# Amplifier.net
KiCad netlist of a schematic drawn in Altium Designer
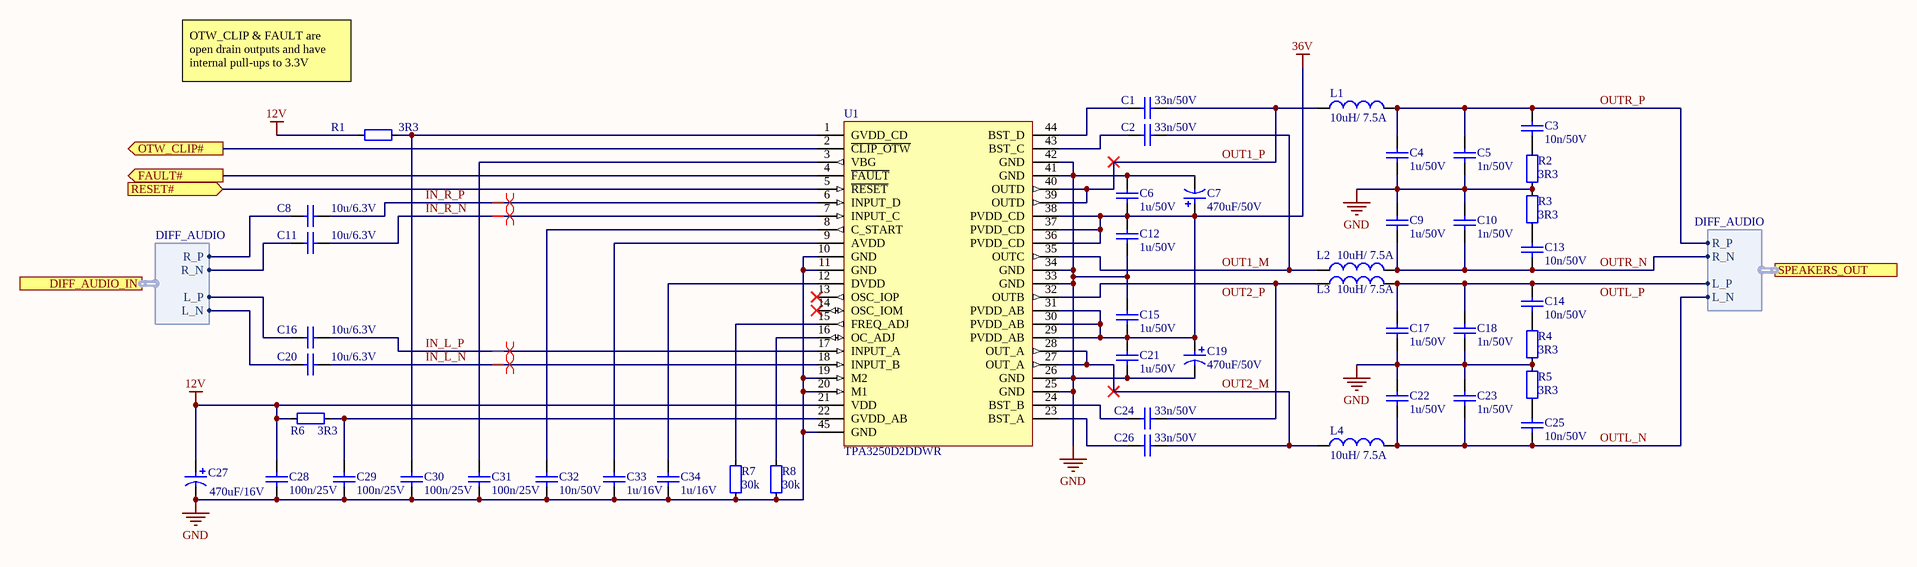
[diagram p0: Amplifier.SchDoc]

(export (version "E")
  (design (tool "Eeschema 10.0.6"))
  (components
    (comp (ref "C1")
      (value "33n/50V")
      (footprint "C0603")
      (fields (field (name "VOLTAGE") "50V") (field (name "TOLERANCE") "10%"))
      (libsource (lib "dk_capacitors") (part "33n 50V X7R 0603"))
    )
    (comp (ref "C2")
      (value "33n/50V")
      (footprint "C0603")
      (fields (field (name "VOLTAGE") "50V") (field (name "TOLERANCE") "10%"))
      (libsource (lib "dk_capacitors") (part "33n 50V X7R 0603"))
    )
    (comp (ref "C3")
      (value "10n/50V")
      (footprint "C0402")
      (fields (field (name "VOLTAGE") "50V") (field (name "TOLERANCE") "10%"))
      (libsource (lib "dk_capacitors") (part "10n 50V X7R 0402"))
    )
    (comp (ref "C4")
      (value "1u/50V")
      (footprint "C2824")
      (fields (field (name "VOLTAGE") "50V") (field (name "TOLERANCE") "5%"))
      (libsource (lib "dk_capacitors") (part "1u 50V PET 2824"))
    )
    (comp (ref "C5")
      (value "1n/50V")
      (footprint "C0402")
      (fields (field (name "VOLTAGE") "50V") (field (name "TOLERANCE") "10%"))
      (libsource (lib "dk_capacitors") (part "1n 50V X7R 0402"))
    )
    (comp (ref "C6")
      (value "1u/50V")
      (footprint "C0805")
      (fields (field (name "VOLTAGE") "50V") (field (name "TOLERANCE") "10%"))
      (libsource (lib "dk_capacitors") (part "1u 50V X7R 0805"))
    )
    (comp (ref "C7")
      (value "470uF/50V")
      (footprint "Wurth-L17-D16")
      (description "Aluminium Electrolytic Capacitors - SMD WCAP-ASLL 50V 470uF 20% ESR=73mOhms")
      (fields (field (name "VOLTAGE") "50V") (field (name "TOLERANCE") "20%"))
      (libsource (lib "dk_electrolytic_caps") (part "Wurth-470uF-50V-L17-D16"))
    )
    (comp (ref "C8")
      (value "10u/6.3V")
      (footprint "C0805")
      (fields (field (name "VOLTAGE") "6.3V") (field (name "TOLERANCE") "10%"))
      (libsource (lib "dk_capacitors") (part "10u 6V3 X7R 0805"))
    )
    (comp (ref "C9")
      (value "1u/50V")
      (footprint "C2824")
      (fields (field (name "VOLTAGE") "50V") (field (name "TOLERANCE") "5%"))
      (libsource (lib "dk_capacitors") (part "1u 50V PET 2824"))
    )
    (comp (ref "C10")
      (value "1n/50V")
      (footprint "C0402")
      (fields (field (name "VOLTAGE") "50V") (field (name "TOLERANCE") "10%"))
      (libsource (lib "dk_capacitors") (part "1n 50V X7R 0402"))
    )
    (comp (ref "C11")
      (value "10u/6.3V")
      (footprint "C0805")
      (fields (field (name "VOLTAGE") "6.3V") (field (name "TOLERANCE") "10%"))
      (libsource (lib "dk_capacitors") (part "10u 6V3 X7R 0805"))
    )
    (comp (ref "C12")
      (value "1u/50V")
      (footprint "C0805")
      (fields (field (name "VOLTAGE") "50V") (field (name "TOLERANCE") "10%"))
      (libsource (lib "dk_capacitors") (part "1u 50V X7R 0805"))
    )
    (comp (ref "C13")
      (value "10n/50V")
      (footprint "C0402")
      (fields (field (name "VOLTAGE") "50V") (field (name "TOLERANCE") "10%"))
      (libsource (lib "dk_capacitors") (part "10n 50V X7R 0402"))
    )
    (comp (ref "C14")
      (value "10n/50V")
      (footprint "C0402")
      (fields (field (name "VOLTAGE") "50V") (field (name "TOLERANCE") "10%"))
      (libsource (lib "dk_capacitors") (part "10n 50V X7R 0402"))
    )
    (comp (ref "C15")
      (value "1u/50V")
      (footprint "C0805")
      (fields (field (name "VOLTAGE") "50V") (field (name "TOLERANCE") "10%"))
      (libsource (lib "dk_capacitors") (part "1u 50V X7R 0805"))
    )
    (comp (ref "C16")
      (value "10u/6.3V")
      (footprint "C0805")
      (fields (field (name "VOLTAGE") "6.3V") (field (name "TOLERANCE") "10%"))
      (libsource (lib "dk_capacitors") (part "10u 6V3 X7R 0805"))
    )
    (comp (ref "C17")
      (value "1u/50V")
      (footprint "C2824")
      (fields (field (name "VOLTAGE") "50V") (field (name "TOLERANCE") "5%"))
      (libsource (lib "dk_capacitors") (part "1u 50V PET 2824"))
    )
    (comp (ref "C18")
      (value "1n/50V")
      (footprint "C0402")
      (fields (field (name "VOLTAGE") "50V") (field (name "TOLERANCE") "10%"))
      (libsource (lib "dk_capacitors") (part "1n 50V X7R 0402"))
    )
    (comp (ref "C19")
      (value "470uF/50V")
      (footprint "Wurth-L17-D16")
      (description "Aluminium Electrolytic Capacitors - SMD WCAP-ASLL 50V 470uF 20% ESR=73mOhms")
      (fields (field (name "VOLTAGE") "50V") (field (name "TOLERANCE") "20%"))
      (libsource (lib "dk_electrolytic_caps") (part "Wurth-470uF-50V-L17-D16"))
    )
    (comp (ref "C20")
      (value "10u/6.3V")
      (footprint "C0805")
      (fields (field (name "VOLTAGE") "6.3V") (field (name "TOLERANCE") "10%"))
      (libsource (lib "dk_capacitors") (part "10u 6V3 X7R 0805"))
    )
    (comp (ref "C21")
      (value "1u/50V")
      (footprint "C0805")
      (fields (field (name "VOLTAGE") "50V") (field (name "TOLERANCE") "10%"))
      (libsource (lib "dk_capacitors") (part "1u 50V X7R 0805"))
    )
    (comp (ref "C22")
      (value "1u/50V")
      (footprint "C2824")
      (fields (field (name "VOLTAGE") "50V") (field (name "TOLERANCE") "5%"))
      (libsource (lib "dk_capacitors") (part "1u 50V PET 2824"))
    )
    (comp (ref "C23")
      (value "1n/50V")
      (footprint "C0402")
      (fields (field (name "VOLTAGE") "50V") (field (name "TOLERANCE") "10%"))
      (libsource (lib "dk_capacitors") (part "1n 50V X7R 0402"))
    )
    (comp (ref "C24")
      (value "33n/50V")
      (footprint "C0603")
      (fields (field (name "VOLTAGE") "50V") (field (name "TOLERANCE") "10%"))
      (libsource (lib "dk_capacitors") (part "33n 50V X7R 0603"))
    )
    (comp (ref "C25")
      (value "10n/50V")
      (footprint "C0402")
      (fields (field (name "VOLTAGE") "50V") (field (name "TOLERANCE") "10%"))
      (libsource (lib "dk_capacitors") (part "10n 50V X7R 0402"))
    )
    (comp (ref "C26")
      (value "33n/50V")
      (footprint "C0603")
      (fields (field (name "VOLTAGE") "50V") (field (name "TOLERANCE") "10%"))
      (libsource (lib "dk_capacitors") (part "33n 50V X7R 0603"))
    )
    (comp (ref "C27")
      (value "470uF/16V")
      (footprint "Wurth-L10.5-D8")
      (description "Aluminium Electrolytic Capacitors - SMD WCAP-ASLI 470uF 16V 20% SMD/SMT")
      (fields (field (name "VOLTAGE") "16V") (field (name "TOLERANCE") "20%"))
      (libsource (lib "dk_electrolytic_caps") (part "Wurth-470uF-16V-L10.5-D8"))
    )
    (comp (ref "C28")
      (value "100n/25V")
      (footprint "C0402")
      (fields (field (name "VOLTAGE") "25V") (field (name "TOLERANCE") "10%"))
      (libsource (lib "dk_capacitors") (part "100n 25V X7R 0402"))
    )
    (comp (ref "C29")
      (value "100n/25V")
      (footprint "C0402")
      (fields (field (name "VOLTAGE") "25V") (field (name "TOLERANCE") "10%"))
      (libsource (lib "dk_capacitors") (part "100n 25V X7R 0402"))
    )
    (comp (ref "C30")
      (value "100n/25V")
      (footprint "C0402")
      (fields (field (name "VOLTAGE") "25V") (field (name "TOLERANCE") "10%"))
      (libsource (lib "dk_capacitors") (part "100n 25V X7R 0402"))
    )
    (comp (ref "C31")
      (value "100n/25V")
      (footprint "C0402")
      (fields (field (name "VOLTAGE") "25V") (field (name "TOLERANCE") "10%"))
      (libsource (lib "dk_capacitors") (part "100n 25V X7R 0402"))
    )
    (comp (ref "C32")
      (value "10n/50V")
      (footprint "C0402")
      (fields (field (name "VOLTAGE") "50V") (field (name "TOLERANCE") "10%"))
      (libsource (lib "dk_capacitors") (part "10n 50V X7R 0402"))
    )
    (comp (ref "C33")
      (value "1u/16V")
      (footprint "C0603")
      (fields (field (name "VOLTAGE") "16V") (field (name "TOLERANCE") "10%"))
      (libsource (lib "dk_capacitors") (part "1u 16V X7R 0603"))
    )
    (comp (ref "C34")
      (value "1u/16V")
      (footprint "C0603")
      (fields (field (name "VOLTAGE") "16V") (field (name "TOLERANCE") "10%"))
      (libsource (lib "dk_capacitors") (part "1u 16V X7R 0603"))
    )
    (comp (ref "L1")
      (value "10uH/ 7.5A")
      (footprint "PA4342.103NLT")
      (description "Fixed Inductors 10uH 7.5A 4mm 20% Low Prof")
      (fields (field (name "TOLERANCE") "20%") (field (name "MANUFACTURER PART NUMBER") "PA4342.103NLT"))
      (libsource (lib "dk_inductors") (part "PA4342.103NLT"))
    )
    (comp (ref "L2")
      (value "10uH/ 7.5A")
      (footprint "PA4342.103NLT")
      (description "Fixed Inductors 10uH 7.5A 4mm 20% Low Prof")
      (fields (field (name "TOLERANCE") "20%") (field (name "MANUFACTURER PART NUMBER") "PA4342.103NLT"))
      (libsource (lib "dk_inductors") (part "PA4342.103NLT"))
    )
    (comp (ref "L3")
      (value "10uH/ 7.5A")
      (footprint "PA4342.103NLT")
      (description "Fixed Inductors 10uH 7.5A 4mm 20% Low Prof")
      (fields (field (name "TOLERANCE") "20%") (field (name "MANUFACTURER PART NUMBER") "PA4342.103NLT"))
      (libsource (lib "dk_inductors") (part "PA4342.103NLT"))
    )
    (comp (ref "L4")
      (value "10uH/ 7.5A")
      (footprint "PA4342.103NLT")
      (description "Fixed Inductors 10uH 7.5A 4mm 20% Low Prof")
      (fields (field (name "TOLERANCE") "20%") (field (name "MANUFACTURER PART NUMBER") "PA4342.103NLT"))
      (libsource (lib "dk_inductors") (part "PA4342.103NLT"))
    )
    (comp (ref "R1")
      (value "3R3")
      (footprint "R0402")
      (fields (field (name "TOLERANCE") "1%") (field (name "VOLTAGE") "50V"))
      (libsource (lib "dk_resistors") (part "3R3 100mW 50V 0402"))
    )
    (comp (ref "R2")
      (value "3R3")
      (footprint "R0402")
      (fields (field (name "TOLERANCE") "1%") (field (name "VOLTAGE") "50V"))
      (libsource (lib "") (part "3R3 100mW 50V 0402_1"))
    )
    (comp (ref "R3")
      (value "3R3")
      (footprint "R0402")
      (fields (field (name "TOLERANCE") "1%") (field (name "VOLTAGE") "50V"))
      (libsource (lib "") (part "3R3 100mW 50V 0402_1"))
    )
    (comp (ref "R4")
      (value "3R3")
      (footprint "R0402")
      (fields (field (name "TOLERANCE") "1%") (field (name "VOLTAGE") "50V"))
      (libsource (lib "") (part "3R3 100mW 50V 0402_1"))
    )
    (comp (ref "R5")
      (value "3R3")
      (footprint "R0402")
      (fields (field (name "TOLERANCE") "1%") (field (name "VOLTAGE") "50V"))
      (libsource (lib "") (part "3R3 100mW 50V 0402_1"))
    )
    (comp (ref "R6")
      (value "3R3")
      (footprint "R0402")
      (fields (field (name "TOLERANCE") "1%") (field (name "VOLTAGE") "50V"))
      (libsource (lib "dk_resistors") (part "3R3 100mW 50V 0402"))
    )
    (comp (ref "R7")
      (value "30k")
      (footprint "R0402")
      (fields (field (name "TOLERANCE") "1%") (field (name "VOLTAGE") "50V"))
      (libsource (lib "dk_resistors") (part "30k 63mW 50V 0402"))
    )
    (comp (ref "R8")
      (value "30k")
      (footprint "R0402")
      (fields (field (name "TOLERANCE") "1%") (field (name "VOLTAGE") "50V"))
      (libsource (lib "dk_resistors") (part "30k 63mW 50V 0402"))
    )
    (comp (ref "U1")
      (value "TPA3250D2DDWR")
      (footprint "HTSSOP-44")
      (description "TPA3250 70-W Stereo, 130-W peak PurePath™ Ultra-HD Pad Down Class-D Amplifier")
      (libsource (lib "dk_ic_audio") (part "TPA3250D2DDWR"))
    )
  )
  (nets
    (net (code "2") (name "/FAULT#") (class "Default")
      (node (ref "U1") (pin "4") (pinfunction "~{FAULT}_4") (pintype "open_collector"))
    )
    (net (code "3") (name "/IN_L_N") (class "Default")
      (node (ref "C20") (pin "2") (pinfunction "2_2") (pintype "passive"))
      (node (ref "U1") (pin "18") (pinfunction "INPUT_B_18") (pintype "input"))
    )
    (net (code "4") (name "/IN_L_P") (class "Default")
      (node (ref "C16") (pin "2") (pinfunction "2_2") (pintype "passive"))
      (node (ref "U1") (pin "17") (pinfunction "INPUT_A_17") (pintype "input"))
    )
    (net (code "5") (name "/IN_R_N") (class "Default")
      (node (ref "C11") (pin "2") (pinfunction "2_2") (pintype "passive"))
      (node (ref "U1") (pin "7") (pinfunction "INPUT_C_7") (pintype "input"))
    )
    (net (code "6") (name "/IN_R_P") (class "Default")
      (node (ref "C8") (pin "2") (pinfunction "2_2") (pintype "passive"))
      (node (ref "U1") (pin "6") (pinfunction "INPUT_D_6") (pintype "input"))
    )
    (net (code "7") (name "/OTW_CLIP#") (class "Default")
      (node (ref "U1") (pin "2") (pinfunction "~{CLIP_OTW}_2") (pintype "open_collector"))
    )
    (net (code "8") (name "/OUT1_M") (class "Default")
      (node (ref "C2") (pin "2") (pinfunction "2_2") (pintype "passive"))
      (node (ref "L2") (pin "1") (pinfunction "1_1") (pintype "passive"))
      (node (ref "U1") (pin "35") (pinfunction "OUTC_35") (pintype "output"))
    )
    (net (code "9") (name "/OUT1_P") (class "Default")
      (node (ref "C1") (pin "2") (pinfunction "2_2") (pintype "passive"))
      (node (ref "L1") (pin "1") (pinfunction "1_1") (pintype "passive"))
      (node (ref "U1") (pin "39") (pinfunction "OUTD_39") (pintype "output"))
      (node (ref "U1") (pin "40") (pinfunction "OUTD_40") (pintype "output"))
    )
    (net (code "10") (name "/OUT2_M") (class "Default")
      (node (ref "C26") (pin "2") (pinfunction "2_2") (pintype "passive"))
      (node (ref "L4") (pin "1") (pinfunction "1_1") (pintype "passive"))
      (node (ref "U1") (pin "27") (pinfunction "OUT_A_27") (pintype "output"))
      (node (ref "U1") (pin "28") (pinfunction "OUT_A_28") (pintype "output"))
    )
    (net (code "11") (name "/OUT2_P") (class "Default")
      (node (ref "C24") (pin "2") (pinfunction "2_2") (pintype "passive"))
      (node (ref "L3") (pin "1") (pinfunction "1_1") (pintype "passive"))
      (node (ref "U1") (pin "32") (pinfunction "OUTB_32") (pintype "output"))
    )
    (net (code "12") (name "/OUTL_N") (class "Default")
      (node (ref "C22") (pin "1") (pinfunction "1_1") (pintype "passive"))
      (node (ref "C23") (pin "1") (pinfunction "1_1") (pintype "passive"))
      (node (ref "C25") (pin "1") (pinfunction "1_1") (pintype "passive"))
      (node (ref "L4") (pin "2") (pinfunction "2_2") (pintype "passive"))
    )
    (net (code "13") (name "/OUTL_P") (class "Default")
      (node (ref "C14") (pin "2") (pinfunction "2_2") (pintype "passive"))
      (node (ref "C17") (pin "2") (pinfunction "2_2") (pintype "passive"))
      (node (ref "C18") (pin "2") (pinfunction "2_2") (pintype "passive"))
      (node (ref "L3") (pin "2") (pinfunction "2_2") (pintype "passive"))
    )
    (net (code "14") (name "/OUTR_N") (class "Default")
      (node (ref "C10") (pin "1") (pinfunction "1_1") (pintype "passive"))
      (node (ref "C13") (pin "1") (pinfunction "1_1") (pintype "passive"))
      (node (ref "C9") (pin "1") (pinfunction "1_1") (pintype "passive"))
      (node (ref "L2") (pin "2") (pinfunction "2_2") (pintype "passive"))
    )
    (net (code "15") (name "/OUTR_P") (class "Default")
      (node (ref "C3") (pin "2") (pinfunction "2_2") (pintype "passive"))
      (node (ref "C4") (pin "2") (pinfunction "2_2") (pintype "passive"))
      (node (ref "C5") (pin "2") (pinfunction "2_2") (pintype "passive"))
      (node (ref "L1") (pin "2") (pinfunction "2_2") (pintype "passive"))
    )
    (net (code "16") (name "/RESET#") (class "Default")
      (node (ref "U1") (pin "5") (pinfunction "~{RESET}_5") (pintype "input"))
    )
    (net (code "18") (name "12V") (class "Default")
      (node (ref "C27") (pin "1") (pinfunction "1_1") (pintype "passive"))
      (node (ref "C28") (pin "2") (pinfunction "2_2") (pintype "passive"))
      (node (ref "R1") (pin "2") (pinfunction "2_2") (pintype "passive"))
      (node (ref "R6") (pin "2") (pinfunction "2_2") (pintype "passive"))
      (node (ref "U1") (pin "21") (pinfunction "VDD_21") (pintype "power_in"))
    )
    (net (code "19") (name "36V") (class "Default")
      (node (ref "C12") (pin "2") (pinfunction "2_2") (pintype "passive"))
      (node (ref "C15") (pin "1") (pinfunction "1_1") (pintype "passive"))
      (node (ref "C19") (pin "1") (pinfunction "1_1") (pintype "passive"))
      (node (ref "C21") (pin "2") (pinfunction "2_2") (pintype "passive"))
      (node (ref "C6") (pin "1") (pinfunction "1_1") (pintype "passive"))
      (node (ref "C7") (pin "1") (pinfunction "1_1") (pintype "passive"))
      (node (ref "U1") (pin "29") (pinfunction "PVDD_AB_29") (pintype "power_in"))
      (node (ref "U1") (pin "30") (pinfunction "PVDD_AB_30") (pintype "power_in"))
      (node (ref "U1") (pin "31") (pinfunction "PVDD_AB_31") (pintype "power_in"))
      (node (ref "U1") (pin "36") (pinfunction "PVDD_CD_36") (pintype "power_in"))
      (node (ref "U1") (pin "37") (pinfunction "PVDD_CD_37") (pintype "power_in"))
      (node (ref "U1") (pin "38") (pinfunction "PVDD_CD_38") (pintype "power_in"))
    )
    (net (code "20") (name "GND") (class "Default")
      (node (ref "C10") (pin "2") (pinfunction "2_2") (pintype "passive"))
      (node (ref "C12") (pin "1") (pinfunction "1_1") (pintype "passive"))
      (node (ref "C15") (pin "2") (pinfunction "2_2") (pintype "passive"))
      (node (ref "C17") (pin "1") (pinfunction "1_1") (pintype "passive"))
      (node (ref "C18") (pin "1") (pinfunction "1_1") (pintype "passive"))
      (node (ref "C19") (pin "2") (pinfunction "2_2") (pintype "passive"))
      (node (ref "C21") (pin "1") (pinfunction "1_1") (pintype "passive"))
      (node (ref "C22") (pin "2") (pinfunction "2_2") (pintype "passive"))
      (node (ref "C23") (pin "2") (pinfunction "2_2") (pintype "passive"))
      (node (ref "C27") (pin "2") (pinfunction "2_2") (pintype "passive"))
      (node (ref "C28") (pin "1") (pinfunction "1_1") (pintype "passive"))
      (node (ref "C29") (pin "1") (pinfunction "1_1") (pintype "passive"))
      (node (ref "C30") (pin "1") (pinfunction "1_1") (pintype "passive"))
      (node (ref "C31") (pin "1") (pinfunction "1_1") (pintype "passive"))
      (node (ref "C32") (pin "1") (pinfunction "1_1") (pintype "passive"))
      (node (ref "C33") (pin "1") (pinfunction "1_1") (pintype "passive"))
      (node (ref "C34") (pin "1") (pinfunction "1_1") (pintype "passive"))
      (node (ref "C4") (pin "1") (pinfunction "1_1") (pintype "passive"))
      (node (ref "C5") (pin "1") (pinfunction "1_1") (pintype "passive"))
      (node (ref "C6") (pin "2") (pinfunction "2_2") (pintype "passive"))
      (node (ref "C7") (pin "2") (pinfunction "2_2") (pintype "passive"))
      (node (ref "C9") (pin "2") (pinfunction "2_2") (pintype "passive"))
      (node (ref "R2") (pin "1") (pinfunction "1_1") (pintype "passive"))
      (node (ref "R3") (pin "2") (pinfunction "2_2") (pintype "passive"))
      (node (ref "R4") (pin "1") (pinfunction "1_1") (pintype "passive"))
      (node (ref "R5") (pin "2") (pinfunction "2_2") (pintype "passive"))
      (node (ref "R7") (pin "1") (pinfunction "1_1") (pintype "passive"))
      (node (ref "R8") (pin "1") (pinfunction "1_1") (pintype "passive"))
      (node (ref "U1") (pin "10") (pinfunction "GND_10") (pintype "power_in"))
      (node (ref "U1") (pin "11") (pinfunction "GND_11") (pintype "power_in"))
      (node (ref "U1") (pin "19") (pinfunction "M2_19") (pintype "input"))
      (node (ref "U1") (pin "20") (pinfunction "M1_20") (pintype "input"))
      (node (ref "U1") (pin "25") (pinfunction "GND_25") (pintype "power_in"))
      (node (ref "U1") (pin "26") (pinfunction "GND_26") (pintype "power_in"))
      (node (ref "U1") (pin "33") (pinfunction "GND_33") (pintype "power_in"))
      (node (ref "U1") (pin "34") (pinfunction "GND_34") (pintype "power_in"))
      (node (ref "U1") (pin "41") (pinfunction "GND_41") (pintype "power_in"))
      (node (ref "U1") (pin "42") (pinfunction "GND_42") (pintype "power_in"))
      (node (ref "U1") (pin "45") (pinfunction "GND_45") (pintype "power_in"))
    )
    (net (code "21") (name "Net-(C3-Pad1)") (class "Default")
      (node (ref "C3") (pin "1") (pinfunction "1_1") (pintype "passive"))
      (node (ref "R2") (pin "2") (pinfunction "2_2") (pintype "passive"))
    )
    (net (code "22") (name "Net-(C13-Pad2)") (class "Default")
      (node (ref "C13") (pin "2") (pinfunction "2_2") (pintype "passive"))
      (node (ref "R3") (pin "1") (pinfunction "1_1") (pintype "passive"))
    )
    (net (code "23") (name "Net-(C14-Pad1)") (class "Default")
      (node (ref "C14") (pin "1") (pinfunction "1_1") (pintype "passive"))
      (node (ref "R4") (pin "2") (pinfunction "2_2") (pintype "passive"))
    )
    (net (code "24") (name "Net-(C25-Pad2)") (class "Default")
      (node (ref "C25") (pin "2") (pinfunction "2_2") (pintype "passive"))
      (node (ref "R5") (pin "1") (pinfunction "1_1") (pintype "passive"))
    )
    (net (code "25") (name "Net-(U1-AVDD)") (class "Default")
      (node (ref "C33") (pin "2") (pinfunction "2_2") (pintype "passive"))
      (node (ref "U1") (pin "9") (pinfunction "AVDD_9") (pintype "power_in"))
    )
    (net (code "26") (name "Net-(U1-BST_A)") (class "Default")
      (node (ref "C26") (pin "1") (pinfunction "1_1") (pintype "passive"))
      (node (ref "U1") (pin "23") (pinfunction "BST_A_23") (pintype "power_in"))
    )
    (net (code "27") (name "Net-(U1-BST_B)") (class "Default")
      (node (ref "C24") (pin "1") (pinfunction "1_1") (pintype "passive"))
      (node (ref "U1") (pin "24") (pinfunction "BST_B_24") (pintype "power_in"))
    )
    (net (code "28") (name "Net-(U1-BST_C)") (class "Default")
      (node (ref "C2") (pin "1") (pinfunction "1_1") (pintype "passive"))
      (node (ref "U1") (pin "43") (pinfunction "BST_C_43") (pintype "power_in"))
    )
    (net (code "29") (name "Net-(U1-BST_D)") (class "Default")
      (node (ref "C1") (pin "1") (pinfunction "1_1") (pintype "passive"))
      (node (ref "U1") (pin "44") (pinfunction "BST_D_44") (pintype "power_in"))
    )
    (net (code "30") (name "Net-(U1-C_START)") (class "Default")
      (node (ref "C32") (pin "2") (pinfunction "2_2") (pintype "passive"))
      (node (ref "U1") (pin "8") (pinfunction "C_START_8") (pintype "output"))
    )
    (net (code "31") (name "Net-(U1-DVDD)") (class "Default")
      (node (ref "C34") (pin "2") (pinfunction "2_2") (pintype "passive"))
      (node (ref "U1") (pin "12") (pinfunction "DVDD_12") (pintype "power_in"))
    )
    (net (code "32") (name "Net-(U1-FREQ_ADJ)") (class "Default")
      (node (ref "R7") (pin "2") (pinfunction "2_2") (pintype "passive"))
      (node (ref "U1") (pin "15") (pinfunction "FREQ_ADJ_15") (pintype "output"))
    )
    (net (code "33") (name "Net-(U1-GVDD_AB)") (class "Default")
      (node (ref "C29") (pin "2") (pinfunction "2_2") (pintype "passive"))
      (node (ref "R6") (pin "1") (pinfunction "1_1") (pintype "passive"))
      (node (ref "U1") (pin "22") (pinfunction "GVDD_AB_22") (pintype "power_in"))
    )
    (net (code "34") (name "Net-(U1-GVDD_CD)") (class "Default")
      (node (ref "C30") (pin "2") (pinfunction "2_2") (pintype "passive"))
      (node (ref "R1") (pin "1") (pinfunction "1_1") (pintype "passive"))
      (node (ref "U1") (pin "1") (pinfunction "GVDD_CD_1") (pintype "power_in"))
    )
    (net (code "35") (name "Net-(U1-OC_ADJ)") (class "Default")
      (node (ref "R8") (pin "2") (pinfunction "2_2") (pintype "passive"))
      (node (ref "U1") (pin "16") (pinfunction "OC_ADJ_16") (pintype "bidirectional"))
    )
    (net (code "36") (name "Net-(U1-VBG)") (class "Default")
      (node (ref "C31") (pin "2") (pinfunction "2_2") (pintype "passive"))
      (node (ref "U1") (pin "3") (pinfunction "VBG_3") (pintype "output"))
    )
    (net (code "37") (name "unconnected-(C8-Pad1)") (class "Default")
      (node (ref "C8") (pin "1") (pinfunction "1_1") (pintype "passive"))
    )
    (net (code "38") (name "unconnected-(C11-Pad1)") (class "Default")
      (node (ref "C11") (pin "1") (pinfunction "1_1") (pintype "passive"))
    )
    (net (code "39") (name "unconnected-(C16-Pad1)") (class "Default")
      (node (ref "C16") (pin "1") (pinfunction "1_1") (pintype "passive"))
    )
    (net (code "40") (name "unconnected-(C20-Pad1)") (class "Default")
      (node (ref "C20") (pin "1") (pinfunction "1_1") (pintype "passive"))
    )
    (net (code "41") (name "unconnected-(U1-OSC_IOM-Pad14)") (class "Default")
      (node (ref "U1") (pin "14") (pinfunction "OSC_IOM_14") (pintype "bidirectional+no_connect"))
    )
    (net (code "42") (name "unconnected-(U1-OSC_IOP-Pad13)") (class "Default")
      (node (ref "U1") (pin "13") (pinfunction "OSC_IOP_13") (pintype "output+no_connect"))
    )
  )
)
